# main.net
KiCad netlist of a schematic drawn in EAGLE
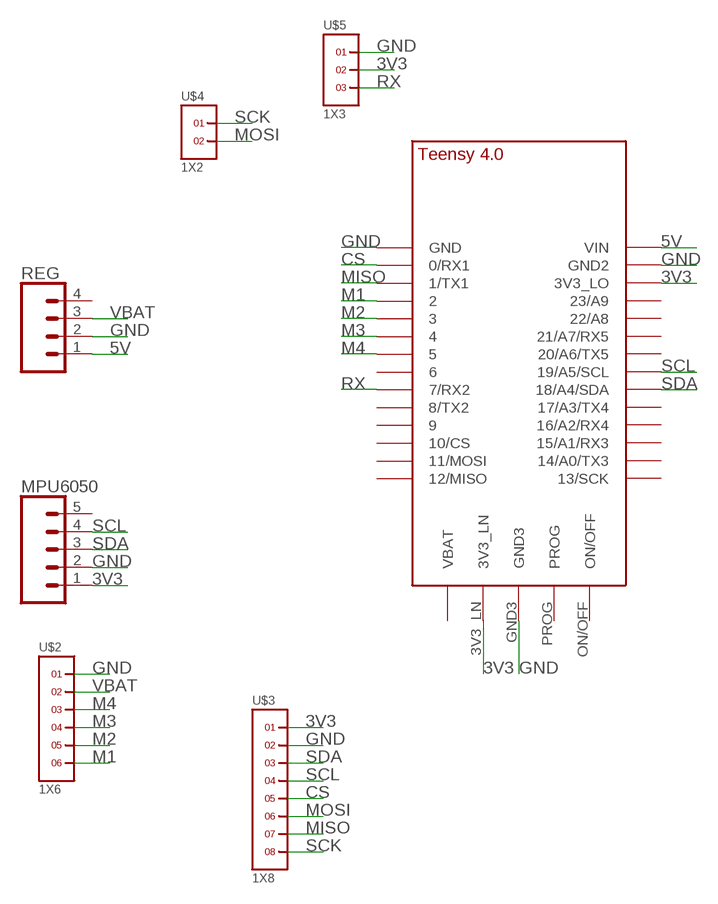
[diagram p0: schematic, sheet 1]

(export (version "E")
  (design (tool "Eeschema 10.0.6"))
  (components
    (comp (ref "MPU6050")
      (value "CONN_05NO_SILK")
      (footprint "eagle-import:1X05_NO_SILK")
      (libsource (lib "eagle-import") (part "CONN_05NO_SILK"))
    )
    (comp (ref "REG")
      (value "CONN_041X04_NO_SILK")
      (footprint "eagle-import:1X04_NO_SILK")
      (libsource (lib "eagle-import") (part "CONN_041X04_NO_SILK"))
    )
    (comp (ref "U$1")
      (value "TEENSY_4.0")
      (footprint "eagle-import:TEENSY_4.0")
      (libsource (lib "eagle-import") (part "TEENSY_4.0"))
    )
    (comp (ref "U$2")
      (value "1X6")
      (footprint "eagle-import:1X6")
      (libsource (lib "eagle-import") (part "1X6"))
    )
    (comp (ref "U$3")
      (value "1X8")
      (footprint "eagle-import:1X8")
      (libsource (lib "eagle-import") (part "1X8"))
    )
    (comp (ref "U$4")
      (value "1X2")
      (footprint "eagle-import:1X2")
      (libsource (lib "eagle-import") (part "1X2"))
    )
    (comp (ref "U$5")
      (value "1X3")
      (footprint "eagle-import:1X3")
      (libsource (lib "eagle-import") (part "1X3"))
    )
  )
  (nets
    (net (code "1") (name "/3V3") (class "Default")
      (node (ref "MPU6050") (pin "1") (pinfunction "1_1") (pintype "passive"))
      (node (ref "U$1") (pin "3V3_LN") (pinfunction "3V3_LN_3V3_LN") (pintype "bidirectional"))
      (node (ref "U$1") (pin "3V3_LO") (pinfunction "3V3_LO_3V3_LO") (pintype "bidirectional"))
      (node (ref "U$3") (pin "1") (pinfunction "1_1") (pintype "bidirectional"))
      (node (ref "U$5") (pin "2") (pinfunction "2_2") (pintype "bidirectional"))
    )
    (net (code "2") (name "/5V") (class "Default")
      (node (ref "REG") (pin "1") (pinfunction "1_1") (pintype "passive"))
      (node (ref "U$1") (pin "VIN") (pinfunction "VIN_VIN") (pintype "bidirectional"))
    )
    (net (code "3") (name "/CS") (class "Default")
      (node (ref "U$1") (pin "0/RX") (pinfunction "0/RX1_0/RX") (pintype "bidirectional"))
      (node (ref "U$3") (pin "5") (pinfunction "5_5") (pintype "bidirectional"))
    )
    (net (code "4") (name "/GND") (class "Default")
      (node (ref "MPU6050") (pin "2") (pinfunction "2_2") (pintype "passive"))
      (node (ref "REG") (pin "2") (pinfunction "2_2") (pintype "passive"))
      (node (ref "U$1") (pin "GND") (pinfunction "GND_GND") (pintype "bidirectional"))
      (node (ref "U$1") (pin "GND2") (pinfunction "GND2_GND2") (pintype "bidirectional"))
      (node (ref "U$1") (pin "GND3") (pinfunction "GND3_GND3") (pintype "bidirectional"))
      (node (ref "U$2") (pin "1") (pinfunction "1_1") (pintype "bidirectional"))
      (node (ref "U$3") (pin "2") (pinfunction "2_2") (pintype "bidirectional"))
      (node (ref "U$5") (pin "1") (pinfunction "1_1") (pintype "bidirectional"))
    )
    (net (code "5") (name "/M1") (class "Default")
      (node (ref "U$1") (pin "2") (pinfunction "2_2") (pintype "bidirectional"))
      (node (ref "U$2") (pin "6") (pinfunction "6_6") (pintype "bidirectional"))
    )
    (net (code "6") (name "/M2") (class "Default")
      (node (ref "U$1") (pin "3/CANTX") (pinfunction "3_3/CANTX") (pintype "bidirectional"))
      (node (ref "U$2") (pin "5") (pinfunction "5_5") (pintype "bidirectional"))
    )
    (net (code "7") (name "/M3") (class "Default")
      (node (ref "U$1") (pin "4/CANRX") (pinfunction "4_4/CANRX") (pintype "bidirectional"))
      (node (ref "U$2") (pin "4") (pinfunction "4_4") (pintype "bidirectional"))
    )
    (net (code "8") (name "/M4") (class "Default")
      (node (ref "U$1") (pin "5") (pinfunction "5_5") (pintype "bidirectional"))
      (node (ref "U$2") (pin "3") (pinfunction "3_3") (pintype "bidirectional"))
    )
    (net (code "9") (name "/MISO") (class "Default")
      (node (ref "U$1") (pin "1/TX") (pinfunction "1/TX1_1/TX") (pintype "bidirectional"))
      (node (ref "U$3") (pin "7") (pinfunction "7_7") (pintype "bidirectional"))
    )
    (net (code "10") (name "/MOSI") (class "Default")
      (node (ref "U$3") (pin "6") (pinfunction "6_6") (pintype "bidirectional"))
      (node (ref "U$4") (pin "2") (pinfunction "2_2") (pintype "bidirectional"))
    )
    (net (code "11") (name "/RX") (class "Default")
      (node (ref "U$1") (pin "7") (pinfunction "7/RX2_7") (pintype "bidirectional"))
      (node (ref "U$5") (pin "3") (pinfunction "3_3") (pintype "bidirectional"))
    )
    (net (code "12") (name "/SCK") (class "Default")
      (node (ref "U$3") (pin "8") (pinfunction "8_8") (pintype "bidirectional"))
      (node (ref "U$4") (pin "1") (pinfunction "1_1") (pintype "bidirectional"))
    )
    (net (code "13") (name "/SCL") (class "Default")
      (node (ref "MPU6050") (pin "4") (pinfunction "4_4") (pintype "passive"))
      (node (ref "U$1") (pin "19/A5/SCL") (pinfunction "19/A5/SCL_19/A5/SCL") (pintype "bidirectional"))
      (node (ref "U$3") (pin "4") (pinfunction "4_4") (pintype "bidirectional"))
    )
    (net (code "14") (name "/SDA") (class "Default")
      (node (ref "MPU6050") (pin "3") (pinfunction "3_3") (pintype "passive"))
      (node (ref "U$1") (pin "18/A4/SDA") (pinfunction "18/A4/SDA_18/A4/SDA") (pintype "bidirectional"))
      (node (ref "U$3") (pin "3") (pinfunction "3_3") (pintype "bidirectional"))
    )
    (net (code "15") (name "/VBAT") (class "Default")
      (node (ref "REG") (pin "3") (pinfunction "3_3") (pintype "passive"))
      (node (ref "U$2") (pin "2") (pinfunction "2_2") (pintype "bidirectional"))
    )
    (net (code "16") (name "unconnected-(MPU6050-Pad5)") (class "Default")
      (node (ref "MPU6050") (pin "5") (pinfunction "5_5") (pintype "passive"))
    )
    (net (code "17") (name "unconnected-(REG-Pad4)") (class "Default")
      (node (ref "REG") (pin "4") (pinfunction "4_4") (pintype "passive"))
    )
    (net (code "18") (name "unconnected-(U$1-8{slash}TX2-Pad8)") (class "Default")
      (node (ref "U$1") (pin "8") (pinfunction "8/TX2_8") (pintype "bidirectional"))
    )
    (net (code "19") (name "unconnected-(U$1-9-Pad9{slash}CS)") (class "Default")
      (node (ref "U$1") (pin "9/CS") (pinfunction "9_9/CS") (pintype "bidirectional"))
    )
    (net (code "20") (name "unconnected-(U$1-14{slash}A0{slash}TX3-Pad14{slash}A0)") (class "Default")
      (node (ref "U$1") (pin "14/A0") (pinfunction "14/A0/TX3_14/A0") (pintype "bidirectional"))
    )
    (net (code "21") (name "unconnected-(U$1-15{slash}A1{slash}RX3-Pad15{slash}A1)") (class "Default")
      (node (ref "U$1") (pin "15/A1") (pinfunction "15/A1/RX3_15/A1") (pintype "bidirectional"))
    )
    (net (code "22") (name "unconnected-(U$1-16{slash}A2{slash}RX4-Pad16{slash}A2)") (class "Default")
      (node (ref "U$1") (pin "16/A2") (pinfunction "16/A2/RX4_16/A2") (pintype "bidirectional"))
    )
    (net (code "23") (name "unconnected-(U$1-17{slash}A3{slash}TX4-Pad17{slash}A3)") (class "Default")
      (node (ref "U$1") (pin "17/A3") (pinfunction "17/A3/TX4_17/A3") (pintype "bidirectional"))
    )
    (net (code "24") (name "unconnected-(U$1-20{slash}A6{slash}TX5-Pad20{slash}A6)") (class "Default")
      (node (ref "U$1") (pin "20/A6") (pinfunction "20/A6/TX5_20/A6") (pintype "bidirectional"))
    )
    (net (code "25") (name "unconnected-(U$1-21{slash}A7{slash}RX5-Pad21{slash}A7)") (class "Default")
      (node (ref "U$1") (pin "21/A7") (pinfunction "21/A7/RX5_21/A7") (pintype "bidirectional"))
    )
    (net (code "26") (name "unconnected-(U$1-Pad6)") (class "Default")
      (node (ref "U$1") (pin "6") (pinfunction "6_6") (pintype "bidirectional"))
    )
    (net (code "27") (name "unconnected-(U$1-Pad10{slash}CS)") (class "Default")
      (node (ref "U$1") (pin "10/CS") (pinfunction "10/CS_10/CS") (pintype "bidirectional"))
    )
    (net (code "28") (name "unconnected-(U$1-Pad11{slash}MOSI)") (class "Default")
      (node (ref "U$1") (pin "11/MOSI") (pinfunction "11/MOSI_11/MOSI") (pintype "bidirectional"))
    )
    (net (code "29") (name "unconnected-(U$1-Pad12{slash}MISO)") (class "Default")
      (node (ref "U$1") (pin "12/MISO") (pinfunction "12/MISO_12/MISO") (pintype "bidirectional"))
    )
    (net (code "30") (name "unconnected-(U$1-Pad13{slash}SCK)") (class "Default")
      (node (ref "U$1") (pin "13/SCK") (pinfunction "13/SCK_13/SCK") (pintype "bidirectional"))
    )
    (net (code "31") (name "unconnected-(U$1-Pad22{slash}A8)") (class "Default")
      (node (ref "U$1") (pin "22/A8") (pinfunction "22/A8_22/A8") (pintype "bidirectional"))
    )
    (net (code "32") (name "unconnected-(U$1-Pad23{slash}A9)") (class "Default")
      (node (ref "U$1") (pin "23/A9") (pinfunction "23/A9_23/A9") (pintype "bidirectional"))
    )
    (net (code "33") (name "unconnected-(U$1-PadON{slash}OFF)") (class "Default")
      (node (ref "U$1") (pin "ON/OFF") (pinfunction "ON/OFF_ON/OFF") (pintype "bidirectional"))
    )
    (net (code "34") (name "unconnected-(U$1-PadPROG)") (class "Default")
      (node (ref "U$1") (pin "PROG") (pinfunction "PROG_PROG") (pintype "bidirectional"))
    )
    (net (code "35") (name "unconnected-(U$1-VBAT-PadVBAT\\)") (class "Default")
      (node (ref "U$1") (pin "VBAT\\") (pinfunction "VBAT_VBAT\\") (pintype "bidirectional"))
    )
  )
)
